# ProDocument_Inexpensive_2023-07-23.net
KiCad netlist of a schematic drawn in EasyEDA Pro
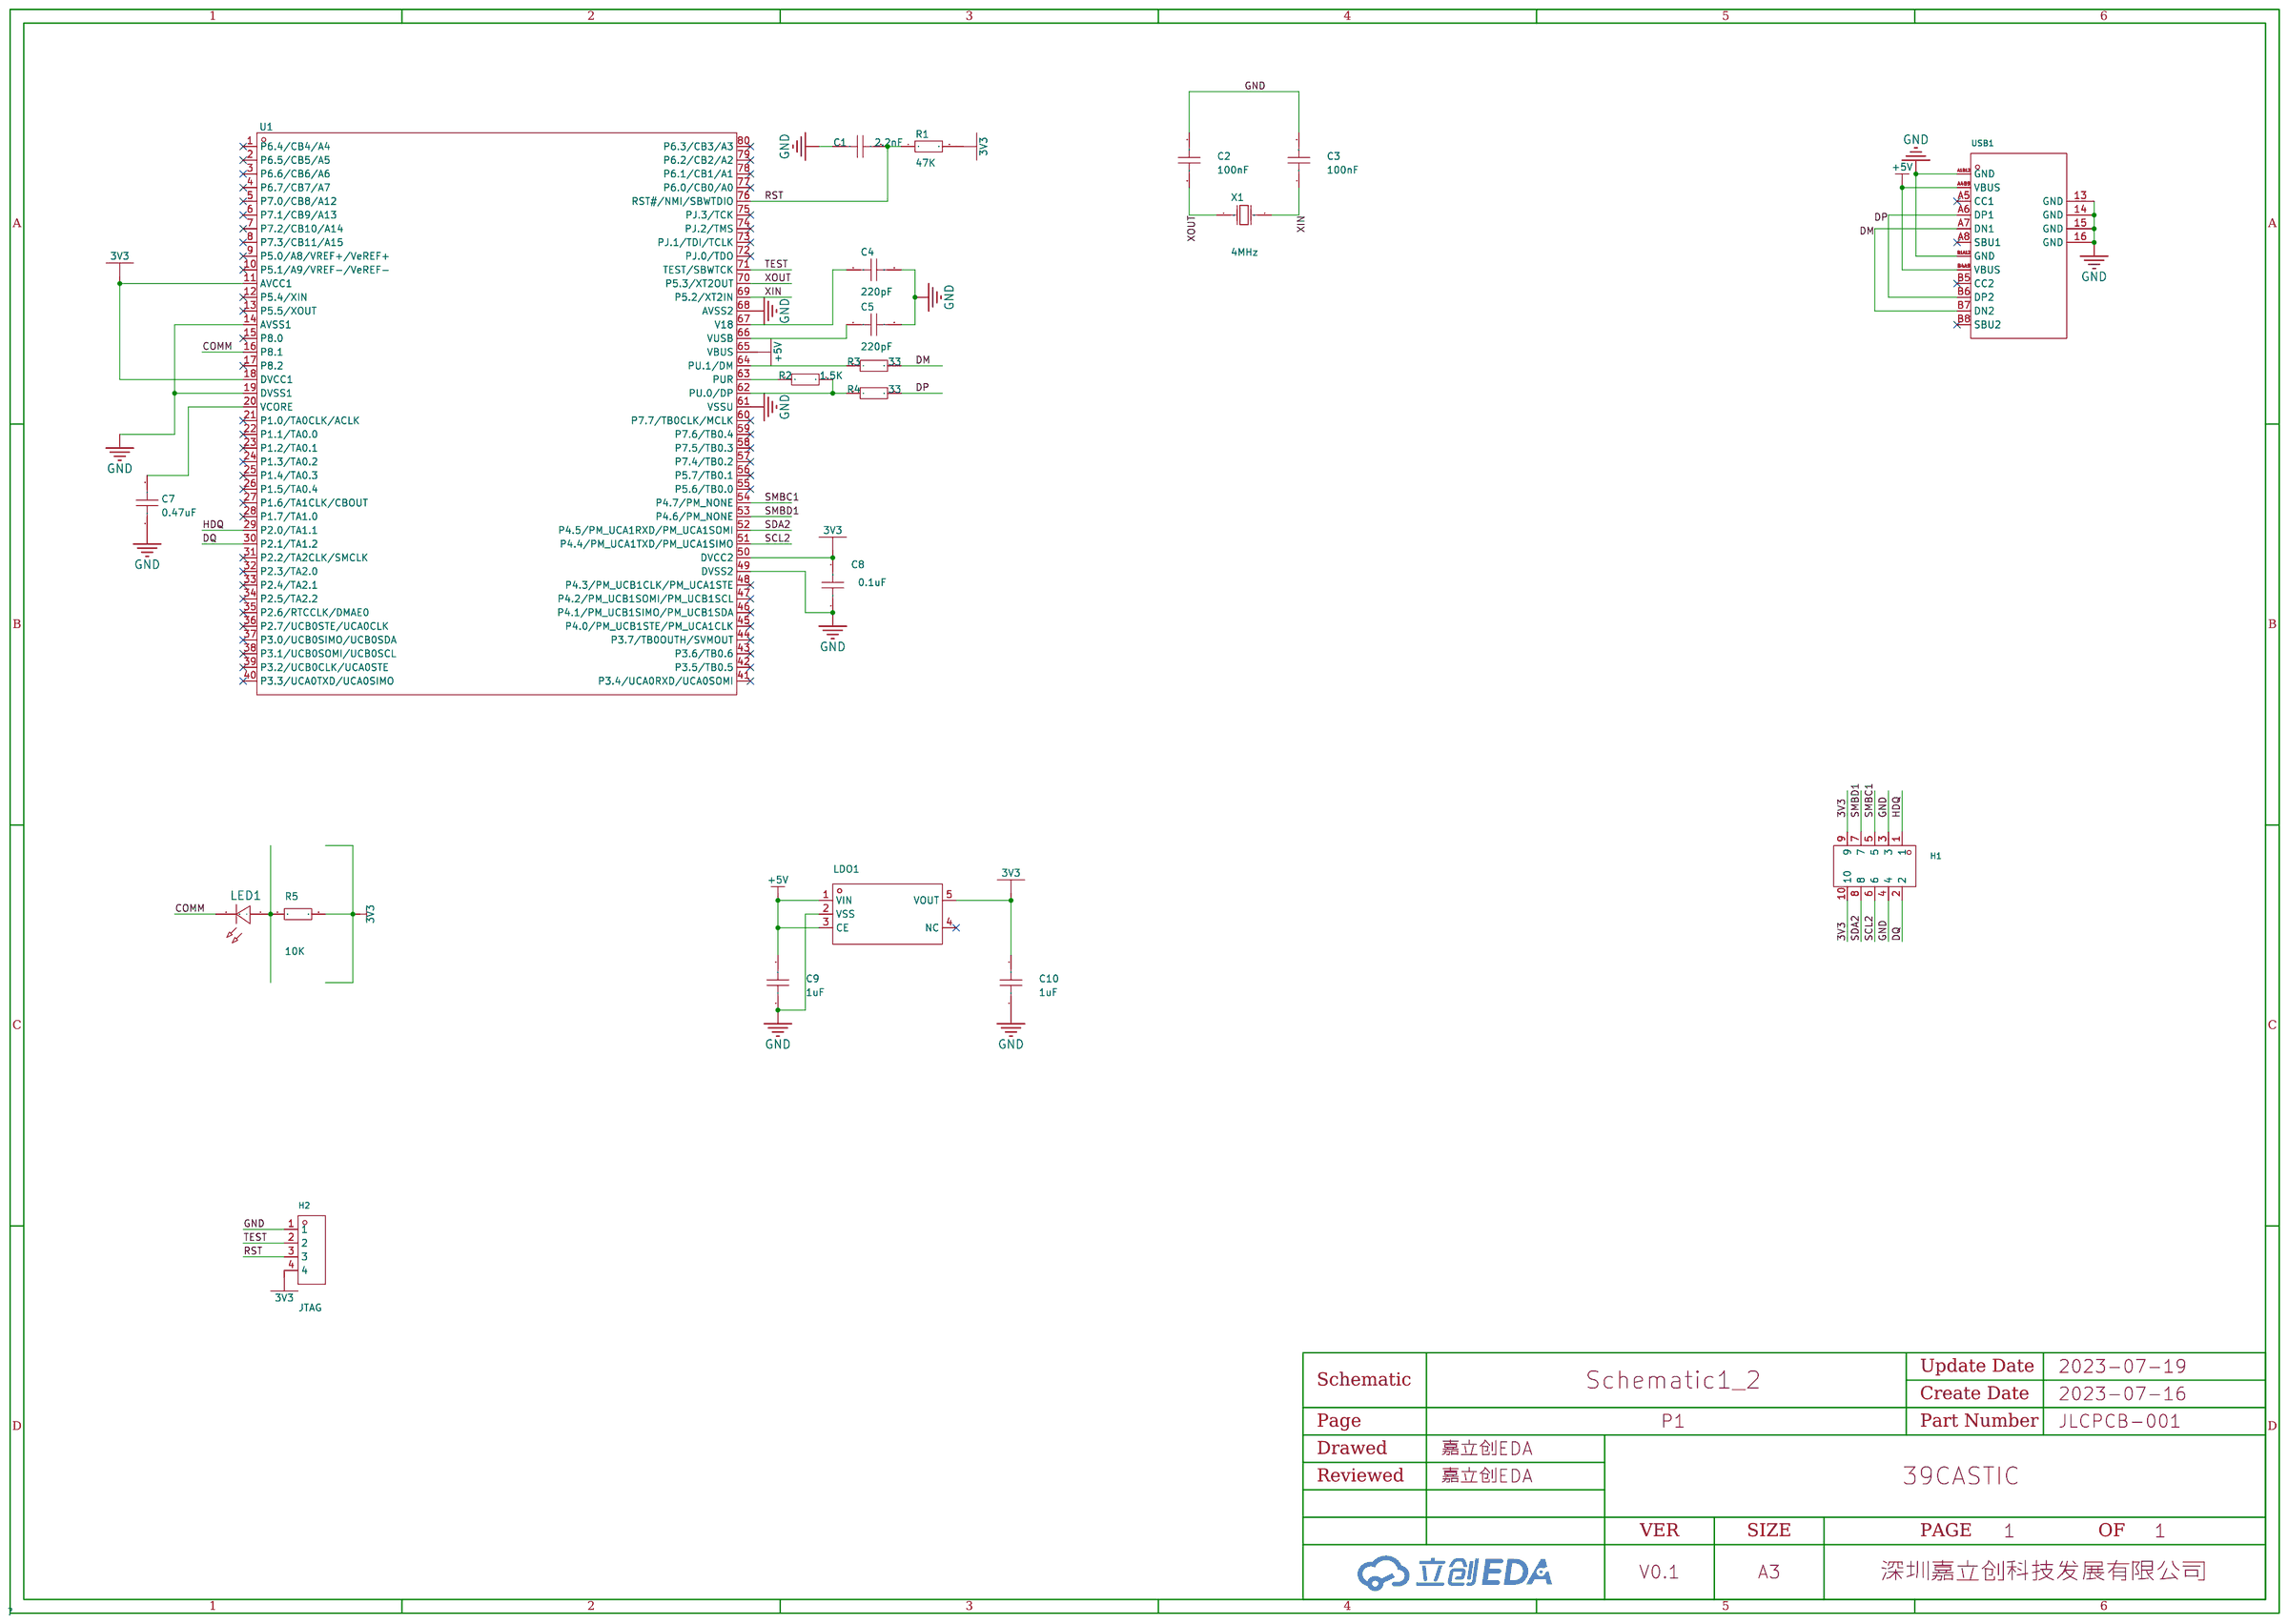
[diagram p0: schematic sheet]

(export (version "E")
  (design (tool "Eeschema 10.0.6"))
  (components
    (comp (ref "C1")
      (value "2.2nF")
      (footprint "easyedapro:C0603_1")
      (description "容值:100nF;精度:±10%;额定电压:50V;温度系数:X7R;")
      (libsource (lib "easyedapro") (part "C1210X7R475K630NT"))
    )
    (comp (ref "C2")
      (value "100nF")
      (footprint "easyedapro:C0603")
      (libsource (lib "easyedapro") (part "CapAcitance"))
    )
    (comp (ref "C3")
      (value "100nF")
      (footprint "easyedapro:C0603")
      (libsource (lib "easyedapro") (part "CapAcitance"))
    )
    (comp (ref "C4")
      (value "220pF")
      (footprint "easyedapro:C0603_1")
      (description "容值:100nF;精度:±10%;额定电压:50V;温度系数:X7R;")
      (libsource (lib "easyedapro") (part "C1210X7R475K630NT"))
    )
    (comp (ref "C5")
      (value "220pF")
      (footprint "easyedapro:C0603_1")
      (description "容值:100nF;精度:±10%;额定电压:50V;温度系数:X7R;")
      (libsource (lib "easyedapro") (part "C1210X7R475K630NT"))
    )
    (comp (ref "C7")
      (value "0.47uF")
      (footprint "easyedapro:C0603_1")
      (description "容值:100nF;精度:±10%;额定电压:50V;温度系数:X7R;")
      (libsource (lib "easyedapro") (part "C1210X7R475K630NT"))
    )
    (comp (ref "C8")
      (value "0.1uF")
      (footprint "easyedapro:C0603_1")
      (description "容值:100nF;精度:±10%;额定电压:50V;温度系数:X7R;")
      (libsource (lib "easyedapro") (part "C1210X7R475K630NT"))
    )
    (comp (ref "C9")
      (value "1uF")
      (footprint "easyedapro:C0603")
      (libsource (lib "easyedapro") (part "CapAcitance"))
    )
    (comp (ref "C10")
      (value "1uF")
      (footprint "easyedapro:C0603")
      (libsource (lib "easyedapro") (part "CapAcitance"))
    )
    (comp (ref "H1")
      (value "PZ254V-12-10P")
      (footprint "easyedapro:HDR-TH_10P-P2.54-V-M-R2-C5-S2.54")
      (fields (field (name "Manufacturer") "XFCN(兴飞)"))
      (libsource (lib "easyedapro") (part "PZ254V-12-10P"))
    )
    (comp (ref "H2")
      (value "JTAG")
      (footprint "easyedapro:HDR-TH_4P-P2.54-V-F")
      (libsource (lib "easyedapro") (part "2.54-1*4P母"))
    )
    (comp (ref "LDO1")
      (value "ME6211C33M5G-N")
      (footprint "easyedapro:SOT-23-5_L3.0-W1.7-P0.95-LS2.8-BL")
      (description "输出类型:固定;输出极性:正;最大输入电压:6V;输出电压:3.3V;输出电流:500mA;电源纹波抑制比(PSRR):70dB;")
      (fields (field (name "Manufacturer") "MICRONE(南京微盟)"))
      (libsource (lib "easyedapro") (part "ME6211C33M5G-N"))
    )
    (comp (ref "LED1")
      (value "~")
      (footprint "easyedapro:LED_0603")
      (libsource (lib "easyedapro") (part "LED_R"))
    )
    (comp (ref "R1")
      (value "47K")
      (footprint "easyedapro:R0603_1")
      (libsource (lib "easyedapro") (part "电阻_1"))
    )
    (comp (ref "R2")
      (value "1.5K")
      (footprint "easyedapro:R0603_1")
      (libsource (lib "easyedapro") (part "电阻_1"))
    )
    (comp (ref "R3")
      (value "33")
      (footprint "easyedapro:R0603_1")
      (libsource (lib "easyedapro") (part "电阻_1"))
    )
    (comp (ref "R4")
      (value "33")
      (footprint "easyedapro:R0603_1")
      (libsource (lib "easyedapro") (part "电阻_1"))
    )
    (comp (ref "R5") (value "10K") (footprint "easyedapro:R0603") (libsource (lib "easyedapro") (part "电阻")))
    (comp (ref "U1")
      (value "~")
      (footprint "easyedapro:LQFP-80_L12.0-W12.0-P0.50-LS14.0-BL")
      (description "CPU位数:-;ROM类型:-;CPU内核:-;主频（MAX):-;工作电压:-;")
      (fields (field (name "Manufacturer Part") "MSP430F5529IPN") (field (name "Manufacturer") "TI(德州仪器)"))
      (libsource (lib "easyedapro") (part "MSP430F5529IPN"))
    )
    (comp (ref "USB1")
      (value "TYPEC-304-BCP16")
      (footprint "easyedapro:USB-C-SMD_TYPEC-304-BCP16")
      (fields (field (name "Manufacturer") "XUNPU(讯普)"))
      (libsource (lib "easyedapro") (part "TYPEC-304-BCP16"))
    )
    (comp (ref "X1")
      (value "4MHz")
      (footprint "easyedapro:HC-49US_L11.5-W4.5-P4.88")
      (description "频率:4MHz;频率公差:±20ppm;负载电容:20pF;")
      (fields (field (name "Manufacturer Part") "X49SD4MSD2SC") (field (name "Manufacturer") "YXC(扬兴晶振)"))
      (libsource (lib "easyedapro") (part "X49SD4MSD2SC"))
    )
  )
  (nets
    (net (code "1") (name "+5V") (class "Default")
      (node (ref "C9") (pin "2") (pinfunction "2_2") (pintype "input"))
      (node (ref "LDO1") (pin "1") (pinfunction "VIN_1") (pintype "input"))
      (node (ref "LDO1") (pin "3") (pinfunction "CE_3") (pintype "input"))
      (node (ref "U1") (pin "65") (pinfunction "VBUS_65") (pintype "input"))
      (node (ref "USB1") (pin "A4B9") (pinfunction "VBUS_A4B9") (pintype "input"))
      (node (ref "USB1") (pin "B4A9") (pinfunction "VBUS_B4A9") (pintype "input"))
    )
    (net (code "2") (name "/COMM") (class "Default")
      (node (ref "LED1") (pin "1") (pinfunction "C_1") (pintype "input"))
      (node (ref "U1") (pin "16") (pinfunction "P8.1_16") (pintype "input"))
    )
    (net (code "3") (name "/DM") (class "Default")
      (node (ref "R3") (pin "2") (pinfunction "2_2") (pintype "input"))
      (node (ref "USB1") (pin "A7") (pinfunction "DN1_A7") (pintype "input"))
      (node (ref "USB1") (pin "B7") (pinfunction "DN2_B7") (pintype "input"))
    )
    (net (code "4") (name "/DP") (class "Default")
      (node (ref "R4") (pin "2") (pinfunction "2_2") (pintype "input"))
      (node (ref "USB1") (pin "A6") (pinfunction "DP1_A6") (pintype "input"))
      (node (ref "USB1") (pin "B6") (pinfunction "DP2_B6") (pintype "input"))
    )
    (net (code "5") (name "/DQ") (class "Default")
      (node (ref "H1") (pin "2") (pinfunction "2_2") (pintype "input"))
      (node (ref "U1") (pin "30") (pinfunction "P2.1/TA1.2_30") (pintype "input"))
    )
    (net (code "6") (name "/HDQ") (class "Default")
      (node (ref "H1") (pin "1") (pinfunction "1_1") (pintype "input"))
      (node (ref "U1") (pin "29") (pinfunction "P2.0/TA1.1_29") (pintype "input"))
    )
    (net (code "7") (name "/RST") (class "Default")
      (node (ref "C1") (pin "2") (pinfunction "2_2") (pintype "input"))
      (node (ref "H2") (pin "3") (pinfunction "3_3") (pintype "input"))
      (node (ref "R1") (pin "1") (pinfunction "1_1") (pintype "input"))
      (node (ref "U1") (pin "76") (pinfunction "RST#/NMI/SBWTDIO_76") (pintype "input"))
    )
    (net (code "8") (name "/SCL2") (class "Default")
      (node (ref "H1") (pin "6") (pinfunction "6_6") (pintype "input"))
      (node (ref "U1") (pin "51") (pinfunction "P4.4/PM_UCA1TXD/PM_UCA1SIMO_51") (pintype "input"))
    )
    (net (code "9") (name "/SDA2") (class "Default")
      (node (ref "H1") (pin "8") (pinfunction "8_8") (pintype "input"))
      (node (ref "U1") (pin "52") (pinfunction "P4.5/PM_UCA1RXD/PM_UCA1SOMI_52") (pintype "input"))
    )
    (net (code "10") (name "/SMBC1") (class "Default")
      (node (ref "H1") (pin "5") (pinfunction "5_5") (pintype "input"))
      (node (ref "U1") (pin "54") (pinfunction "P4.7/PM_NONE_54") (pintype "input"))
    )
    (net (code "11") (name "/SMBD1") (class "Default")
      (node (ref "H1") (pin "7") (pinfunction "7_7") (pintype "input"))
      (node (ref "U1") (pin "53") (pinfunction "P4.6/PM_NONE_53") (pintype "input"))
    )
    (net (code "12") (name "/TEST") (class "Default")
      (node (ref "H2") (pin "2") (pinfunction "2_2") (pintype "input"))
      (node (ref "U1") (pin "71") (pinfunction "TEST/SBWTCK_71") (pintype "input"))
    )
    (net (code "13") (name "/XIN") (class "Default")
      (node (ref "C3") (pin "1") (pinfunction "1_1") (pintype "input"))
      (node (ref "U1") (pin "69") (pinfunction "P5.2/XT2IN_69") (pintype "input"))
      (node (ref "X1") (pin "1") (pinfunction "OSC1_1") (pintype "input"))
    )
    (net (code "14") (name "/XOUT") (class "Default")
      (node (ref "C2") (pin "1") (pinfunction "1_1") (pintype "input"))
      (node (ref "U1") (pin "70") (pinfunction "P5.3/XT2OUT_70") (pintype "input"))
      (node (ref "X1") (pin "2") (pinfunction "OSC2_2") (pintype "input"))
    )
    (net (code "15") (name "3V3") (class "Default")
      (node (ref "C10") (pin "2") (pinfunction "2_2") (pintype "input"))
      (node (ref "C8") (pin "2") (pinfunction "2_2") (pintype "input"))
      (node (ref "H1") (pin "10") (pinfunction "10_10") (pintype "input"))
      (node (ref "H1") (pin "9") (pinfunction "9_9") (pintype "input"))
      (node (ref "H2") (pin "4") (pinfunction "4_4") (pintype "input"))
      (node (ref "LDO1") (pin "5") (pinfunction "VOUT_5") (pintype "input"))
      (node (ref "R1") (pin "2") (pinfunction "2_2") (pintype "input"))
      (node (ref "R5") (pin "2") (pinfunction "2_2") (pintype "input"))
      (node (ref "U1") (pin "11") (pinfunction "AVCC1_11") (pintype "input"))
      (node (ref "U1") (pin "18") (pinfunction "DVCC1_18") (pintype "input"))
      (node (ref "U1") (pin "50") (pinfunction "DVCC2_50") (pintype "input"))
    )
    (net (code "16") (name "GND") (class "Default")
      (node (ref "C1") (pin "1") (pinfunction "1_1") (pintype "input"))
      (node (ref "C10") (pin "1") (pinfunction "1_1") (pintype "input"))
      (node (ref "C2") (pin "2") (pinfunction "2_2") (pintype "input"))
      (node (ref "C3") (pin "2") (pinfunction "2_2") (pintype "input"))
      (node (ref "C4") (pin "2") (pinfunction "2_2") (pintype "input"))
      (node (ref "C5") (pin "2") (pinfunction "2_2") (pintype "input"))
      (node (ref "C7") (pin "1") (pinfunction "1_1") (pintype "input"))
      (node (ref "C8") (pin "1") (pinfunction "1_1") (pintype "input"))
      (node (ref "C9") (pin "1") (pinfunction "1_1") (pintype "input"))
      (node (ref "H1") (pin "3") (pinfunction "3_3") (pintype "input"))
      (node (ref "H1") (pin "4") (pinfunction "4_4") (pintype "input"))
      (node (ref "H2") (pin "1") (pinfunction "1_1") (pintype "input"))
      (node (ref "LDO1") (pin "2") (pinfunction "VSS_2") (pintype "input"))
      (node (ref "U1") (pin "14") (pinfunction "AVSS1_14") (pintype "input"))
      (node (ref "U1") (pin "19") (pinfunction "DVSS1_19") (pintype "input"))
      (node (ref "U1") (pin "49") (pinfunction "DVSS2_49") (pintype "input"))
      (node (ref "U1") (pin "61") (pinfunction "VSSU_61") (pintype "input"))
      (node (ref "U1") (pin "68") (pinfunction "AVSS2_68") (pintype "input"))
      (node (ref "USB1") (pin "13") (pinfunction "GND_13") (pintype "input"))
      (node (ref "USB1") (pin "14") (pinfunction "GND_14") (pintype "input"))
      (node (ref "USB1") (pin "15") (pinfunction "GND_15") (pintype "input"))
      (node (ref "USB1") (pin "16") (pinfunction "GND_16") (pintype "input"))
      (node (ref "USB1") (pin "A1B12") (pinfunction "GND_A1B12") (pintype "input"))
      (node (ref "USB1") (pin "B1A12") (pinfunction "GND_B1A12") (pintype "input"))
    )
    (net (code "17") (name "Net-(LED1-A)") (class "Default")
      (node (ref "LED1") (pin "2") (pinfunction "A_2") (pintype "input"))
      (node (ref "R5") (pin "1") (pinfunction "1_1") (pintype "input"))
    )
    (net (code "18") (name "Net-(U1-PU.0{slash}DP)") (class "Default")
      (node (ref "R2") (pin "2") (pinfunction "2_2") (pintype "input"))
      (node (ref "R4") (pin "1") (pinfunction "1_1") (pintype "input"))
      (node (ref "U1") (pin "62") (pinfunction "PU.0/DP_62") (pintype "input"))
    )
    (net (code "19") (name "Net-(U1-PU.1{slash}DM)") (class "Default")
      (node (ref "R3") (pin "1") (pinfunction "1_1") (pintype "input"))
      (node (ref "U1") (pin "64") (pinfunction "PU.1/DM_64") (pintype "input"))
    )
    (net (code "20") (name "Net-(U1-PUR)") (class "Default")
      (node (ref "R2") (pin "1") (pinfunction "1_1") (pintype "input"))
      (node (ref "U1") (pin "63") (pinfunction "PUR_63") (pintype "input"))
    )
    (net (code "21") (name "Net-(U1-V18)") (class "Default")
      (node (ref "C4") (pin "1") (pinfunction "1_1") (pintype "input"))
      (node (ref "U1") (pin "67") (pinfunction "V18_67") (pintype "input"))
    )
    (net (code "22") (name "Net-(U1-VCORE)") (class "Default")
      (node (ref "C7") (pin "2") (pinfunction "2_2") (pintype "input"))
      (node (ref "U1") (pin "20") (pinfunction "VCORE_20") (pintype "input"))
    )
    (net (code "23") (name "Net-(U1-VUSB)") (class "Default")
      (node (ref "C5") (pin "1") (pinfunction "1_1") (pintype "input"))
      (node (ref "U1") (pin "66") (pinfunction "VUSB_66") (pintype "input"))
    )
    (net (code "24") (name "unconnected-(LDO1-NC-Pad4)") (class "Default")
      (node (ref "LDO1") (pin "4") (pinfunction "NC_4") (pintype "input+no_connect"))
    )
    (net (code "25") (name "unconnected-(U1-P1.0{slash}TA0CLK{slash}ACLK-Pad21)") (class "Default")
      (node (ref "U1") (pin "21") (pinfunction "P1.0/TA0CLK/ACLK_21") (pintype "input+no_connect"))
    )
    (net (code "26") (name "unconnected-(U1-P1.1{slash}TA0.0-Pad22)") (class "Default")
      (node (ref "U1") (pin "22") (pinfunction "P1.1/TA0.0_22") (pintype "input+no_connect"))
    )
    (net (code "27") (name "unconnected-(U1-P1.2{slash}TA0.1-Pad23)") (class "Default")
      (node (ref "U1") (pin "23") (pinfunction "P1.2/TA0.1_23") (pintype "input+no_connect"))
    )
    (net (code "28") (name "unconnected-(U1-P1.3{slash}TA0.2-Pad24)") (class "Default")
      (node (ref "U1") (pin "24") (pinfunction "P1.3/TA0.2_24") (pintype "input+no_connect"))
    )
    (net (code "29") (name "unconnected-(U1-P1.4{slash}TA0.3-Pad25)") (class "Default")
      (node (ref "U1") (pin "25") (pinfunction "P1.4/TA0.3_25") (pintype "input+no_connect"))
    )
    (net (code "30") (name "unconnected-(U1-P1.5{slash}TA0.4-Pad26)") (class "Default")
      (node (ref "U1") (pin "26") (pinfunction "P1.5/TA0.4_26") (pintype "input+no_connect"))
    )
    (net (code "31") (name "unconnected-(U1-P1.6{slash}TA1CLK{slash}CBOUT-Pad27)") (class "Default")
      (node (ref "U1") (pin "27") (pinfunction "P1.6/TA1CLK/CBOUT_27") (pintype "input+no_connect"))
    )
    (net (code "32") (name "unconnected-(U1-P1.7{slash}TA1.0-Pad28)") (class "Default")
      (node (ref "U1") (pin "28") (pinfunction "P1.7/TA1.0_28") (pintype "input+no_connect"))
    )
    (net (code "33") (name "unconnected-(U1-P2.2{slash}TA2CLK{slash}SMCLK-Pad31)") (class "Default")
      (node (ref "U1") (pin "31") (pinfunction "P2.2/TA2CLK/SMCLK_31") (pintype "input+no_connect"))
    )
    (net (code "34") (name "unconnected-(U1-P2.3{slash}TA2.0-Pad32)") (class "Default")
      (node (ref "U1") (pin "32") (pinfunction "P2.3/TA2.0_32") (pintype "input+no_connect"))
    )
    (net (code "35") (name "unconnected-(U1-P2.4{slash}TA2.1-Pad33)") (class "Default")
      (node (ref "U1") (pin "33") (pinfunction "P2.4/TA2.1_33") (pintype "input+no_connect"))
    )
    (net (code "36") (name "unconnected-(U1-P2.5{slash}TA2.2-Pad34)") (class "Default")
      (node (ref "U1") (pin "34") (pinfunction "P2.5/TA2.2_34") (pintype "input+no_connect"))
    )
    (net (code "37") (name "unconnected-(U1-P2.6{slash}RTCCLK{slash}DMAE0-Pad35)") (class "Default")
      (node (ref "U1") (pin "35") (pinfunction "P2.6/RTCCLK/DMAE0_35") (pintype "input+no_connect"))
    )
    (net (code "38") (name "unconnected-(U1-P2.7{slash}UCB0STE{slash}UCA0CLK-Pad36)") (class "Default")
      (node (ref "U1") (pin "36") (pinfunction "P2.7/UCB0STE/UCA0CLK_36") (pintype "input+no_connect"))
    )
    (net (code "39") (name "unconnected-(U1-P3.0{slash}UCB0SIMO{slash}UCB0SDA-Pad37)") (class "Default")
      (node (ref "U1") (pin "37") (pinfunction "P3.0/UCB0SIMO/UCB0SDA_37") (pintype "input+no_connect"))
    )
    (net (code "40") (name "unconnected-(U1-P3.1{slash}UCB0SOMI{slash}UCB0SCL-Pad38)") (class "Default")
      (node (ref "U1") (pin "38") (pinfunction "P3.1/UCB0SOMI/UCB0SCL_38") (pintype "input+no_connect"))
    )
    (net (code "41") (name "unconnected-(U1-P3.2{slash}UCB0CLK{slash}UCA0STE-Pad39)") (class "Default")
      (node (ref "U1") (pin "39") (pinfunction "P3.2/UCB0CLK/UCA0STE_39") (pintype "input+no_connect"))
    )
    (net (code "42") (name "unconnected-(U1-P3.3{slash}UCA0TXD{slash}UCA0SIMO-Pad40)") (class "Default")
      (node (ref "U1") (pin "40") (pinfunction "P3.3/UCA0TXD/UCA0SIMO_40") (pintype "input+no_connect"))
    )
    (net (code "43") (name "unconnected-(U1-P3.4{slash}UCA0RXD{slash}UCA0SOMI-Pad41)") (class "Default")
      (node (ref "U1") (pin "41") (pinfunction "P3.4/UCA0RXD/UCA0SOMI_41") (pintype "input+no_connect"))
    )
    (net (code "44") (name "unconnected-(U1-P3.5{slash}TB0.5-Pad42)") (class "Default")
      (node (ref "U1") (pin "42") (pinfunction "P3.5/TB0.5_42") (pintype "input+no_connect"))
    )
    (net (code "45") (name "unconnected-(U1-P3.6{slash}TB0.6-Pad43)") (class "Default")
      (node (ref "U1") (pin "43") (pinfunction "P3.6/TB0.6_43") (pintype "input+no_connect"))
    )
    (net (code "46") (name "unconnected-(U1-P3.7{slash}TB0OUTH{slash}SVMOUT-Pad44)") (class "Default")
      (node (ref "U1") (pin "44") (pinfunction "P3.7/TB0OUTH/SVMOUT_44") (pintype "input+no_connect"))
    )
    (net (code "47") (name "unconnected-(U1-P4.0{slash}PM_UCB1STE{slash}PM_UCA1CLK-Pad45)") (class "Default")
      (node (ref "U1") (pin "45") (pinfunction "P4.0/PM_UCB1STE/PM_UCA1CLK_45") (pintype "input+no_connect"))
    )
    (net (code "48") (name "unconnected-(U1-P4.1{slash}PM_UCB1SIMO{slash}PM_UCB1SDA-Pad46)") (class "Default")
      (node (ref "U1") (pin "46") (pinfunction "P4.1/PM_UCB1SIMO/PM_UCB1SDA_46") (pintype "input+no_connect"))
    )
    (net (code "49") (name "unconnected-(U1-P4.2{slash}PM_UCB1SOMI{slash}PM_UCB1SCL-Pad47)") (class "Default")
      (node (ref "U1") (pin "47") (pinfunction "P4.2/PM_UCB1SOMI/PM_UCB1SCL_47") (pintype "input+no_connect"))
    )
    (net (code "50") (name "unconnected-(U1-P4.3{slash}PM_UCB1CLK{slash}PM_UCA1STE-Pad48)") (class "Default")
      (node (ref "U1") (pin "48") (pinfunction "P4.3/PM_UCB1CLK/PM_UCA1STE_48") (pintype "input+no_connect"))
    )
    (net (code "51") (name "unconnected-(U1-P5.0{slash}A8{slash}VREF+{slash}VeREF+-Pad9)") (class "Default")
      (node (ref "U1") (pin "9") (pinfunction "P5.0/A8/VREF+/VeREF+_9") (pintype "input+no_connect"))
    )
    (net (code "52") (name "unconnected-(U1-P5.1{slash}A9{slash}VREF-{slash}VeREF--Pad10)") (class "Default")
      (node (ref "U1") (pin "10") (pinfunction "P5.1/A9/VREF-/VeREF-_10") (pintype "input+no_connect"))
    )
    (net (code "53") (name "unconnected-(U1-P5.4{slash}XIN-Pad12)") (class "Default")
      (node (ref "U1") (pin "12") (pinfunction "P5.4/XIN_12") (pintype "input+no_connect"))
    )
    (net (code "54") (name "unconnected-(U1-P5.5{slash}XOUT-Pad13)") (class "Default")
      (node (ref "U1") (pin "13") (pinfunction "P5.5/XOUT_13") (pintype "input+no_connect"))
    )
    (net (code "55") (name "unconnected-(U1-P5.6{slash}TB0.0-Pad55)") (class "Default")
      (node (ref "U1") (pin "55") (pinfunction "P5.6/TB0.0_55") (pintype "input+no_connect"))
    )
    (net (code "56") (name "unconnected-(U1-P5.7{slash}TB0.1-Pad56)") (class "Default")
      (node (ref "U1") (pin "56") (pinfunction "P5.7/TB0.1_56") (pintype "input+no_connect"))
    )
    (net (code "57") (name "unconnected-(U1-P6.0{slash}CB0{slash}A0-Pad77)") (class "Default")
      (node (ref "U1") (pin "77") (pinfunction "P6.0/CB0/A0_77") (pintype "input+no_connect"))
    )
    (net (code "58") (name "unconnected-(U1-P6.1{slash}CB1{slash}A1-Pad78)") (class "Default")
      (node (ref "U1") (pin "78") (pinfunction "P6.1/CB1/A1_78") (pintype "input+no_connect"))
    )
    (net (code "59") (name "unconnected-(U1-P6.2{slash}CB2{slash}A2-Pad79)") (class "Default")
      (node (ref "U1") (pin "79") (pinfunction "P6.2/CB2/A2_79") (pintype "input+no_connect"))
    )
    (net (code "60") (name "unconnected-(U1-P6.3{slash}CB3{slash}A3-Pad80)") (class "Default")
      (node (ref "U1") (pin "80") (pinfunction "P6.3/CB3/A3_80") (pintype "input+no_connect"))
    )
    (net (code "61") (name "unconnected-(U1-P6.4{slash}CB4{slash}A4-Pad1)") (class "Default")
      (node (ref "U1") (pin "1") (pinfunction "P6.4/CB4/A4_1") (pintype "input+no_connect"))
    )
    (net (code "62") (name "unconnected-(U1-P6.5{slash}CB5{slash}A5-Pad2)") (class "Default")
      (node (ref "U1") (pin "2") (pinfunction "P6.5/CB5/A5_2") (pintype "input+no_connect"))
    )
    (net (code "63") (name "unconnected-(U1-P6.6{slash}CB6{slash}A6-Pad3)") (class "Default")
      (node (ref "U1") (pin "3") (pinfunction "P6.6/CB6/A6_3") (pintype "input+no_connect"))
    )
    (net (code "64") (name "unconnected-(U1-P6.7{slash}CB7{slash}A7-Pad4)") (class "Default")
      (node (ref "U1") (pin "4") (pinfunction "P6.7/CB7/A7_4") (pintype "input+no_connect"))
    )
    (net (code "65") (name "unconnected-(U1-P7.0{slash}CB8{slash}A12-Pad5)") (class "Default")
      (node (ref "U1") (pin "5") (pinfunction "P7.0/CB8/A12_5") (pintype "input+no_connect"))
    )
    (net (code "66") (name "unconnected-(U1-P7.1{slash}CB9{slash}A13-Pad6)") (class "Default")
      (node (ref "U1") (pin "6") (pinfunction "P7.1/CB9/A13_6") (pintype "input+no_connect"))
    )
    (net (code "67") (name "unconnected-(U1-P7.2{slash}CB10{slash}A14-Pad7)") (class "Default")
      (node (ref "U1") (pin "7") (pinfunction "P7.2/CB10/A14_7") (pintype "input+no_connect"))
    )
    (net (code "68") (name "unconnected-(U1-P7.3{slash}CB11{slash}A15-Pad8)") (class "Default")
      (node (ref "U1") (pin "8") (pinfunction "P7.3/CB11/A15_8") (pintype "input+no_connect"))
    )
    (net (code "69") (name "unconnected-(U1-P7.4{slash}TB0.2-Pad57)") (class "Default")
      (node (ref "U1") (pin "57") (pinfunction "P7.4/TB0.2_57") (pintype "input+no_connect"))
    )
    (net (code "70") (name "unconnected-(U1-P7.5{slash}TB0.3-Pad58)") (class "Default")
      (node (ref "U1") (pin "58") (pinfunction "P7.5/TB0.3_58") (pintype "input+no_connect"))
    )
    (net (code "71") (name "unconnected-(U1-P7.6{slash}TB0.4-Pad59)") (class "Default")
      (node (ref "U1") (pin "59") (pinfunction "P7.6/TB0.4_59") (pintype "input+no_connect"))
    )
    (net (code "72") (name "unconnected-(U1-P7.7{slash}TB0CLK{slash}MCLK-Pad60)") (class "Default")
      (node (ref "U1") (pin "60") (pinfunction "P7.7/TB0CLK/MCLK_60") (pintype "input+no_connect"))
    )
    (net (code "73") (name "unconnected-(U1-P8.0-Pad15)") (class "Default")
      (node (ref "U1") (pin "15") (pinfunction "P8.0_15") (pintype "input+no_connect"))
    )
    (net (code "74") (name "unconnected-(U1-P8.2-Pad17)") (class "Default")
      (node (ref "U1") (pin "17") (pinfunction "P8.2_17") (pintype "input+no_connect"))
    )
    (net (code "75") (name "unconnected-(U1-PJ.0{slash}TDO-Pad72)") (class "Default")
      (node (ref "U1") (pin "72") (pinfunction "PJ.0/TDO_72") (pintype "input+no_connect"))
    )
    (net (code "76") (name "unconnected-(U1-PJ.1{slash}TDI{slash}TCLK-Pad73)") (class "Default")
      (node (ref "U1") (pin "73") (pinfunction "PJ.1/TDI/TCLK_73") (pintype "input+no_connect"))
    )
    (net (code "77") (name "unconnected-(U1-PJ.2{slash}TMS-Pad74)") (class "Default")
      (node (ref "U1") (pin "74") (pinfunction "PJ.2/TMS_74") (pintype "input+no_connect"))
    )
    (net (code "78") (name "unconnected-(U1-PJ.3{slash}TCK-Pad75)") (class "Default")
      (node (ref "U1") (pin "75") (pinfunction "PJ.3/TCK_75") (pintype "input+no_connect"))
    )
    (net (code "79") (name "unconnected-(USB1-CC1-PadA5)") (class "Default")
      (node (ref "USB1") (pin "A5") (pinfunction "CC1_A5") (pintype "input+no_connect"))
    )
    (net (code "80") (name "unconnected-(USB1-CC2-PadB5)") (class "Default")
      (node (ref "USB1") (pin "B5") (pinfunction "CC2_B5") (pintype "input+no_connect"))
    )
    (net (code "81") (name "unconnected-(USB1-SBU1-PadA8)") (class "Default")
      (node (ref "USB1") (pin "A8") (pinfunction "SBU1_A8") (pintype "input+no_connect"))
    )
    (net (code "82") (name "unconnected-(USB1-SBU2-PadB8)") (class "Default")
      (node (ref "USB1") (pin "B8") (pinfunction "SBU2_B8") (pintype "input+no_connect"))
    )
  )
)
